# JacdacRgbBar8Ec30_122.net
KiCad netlist of a schematic drawn in Altium Designer
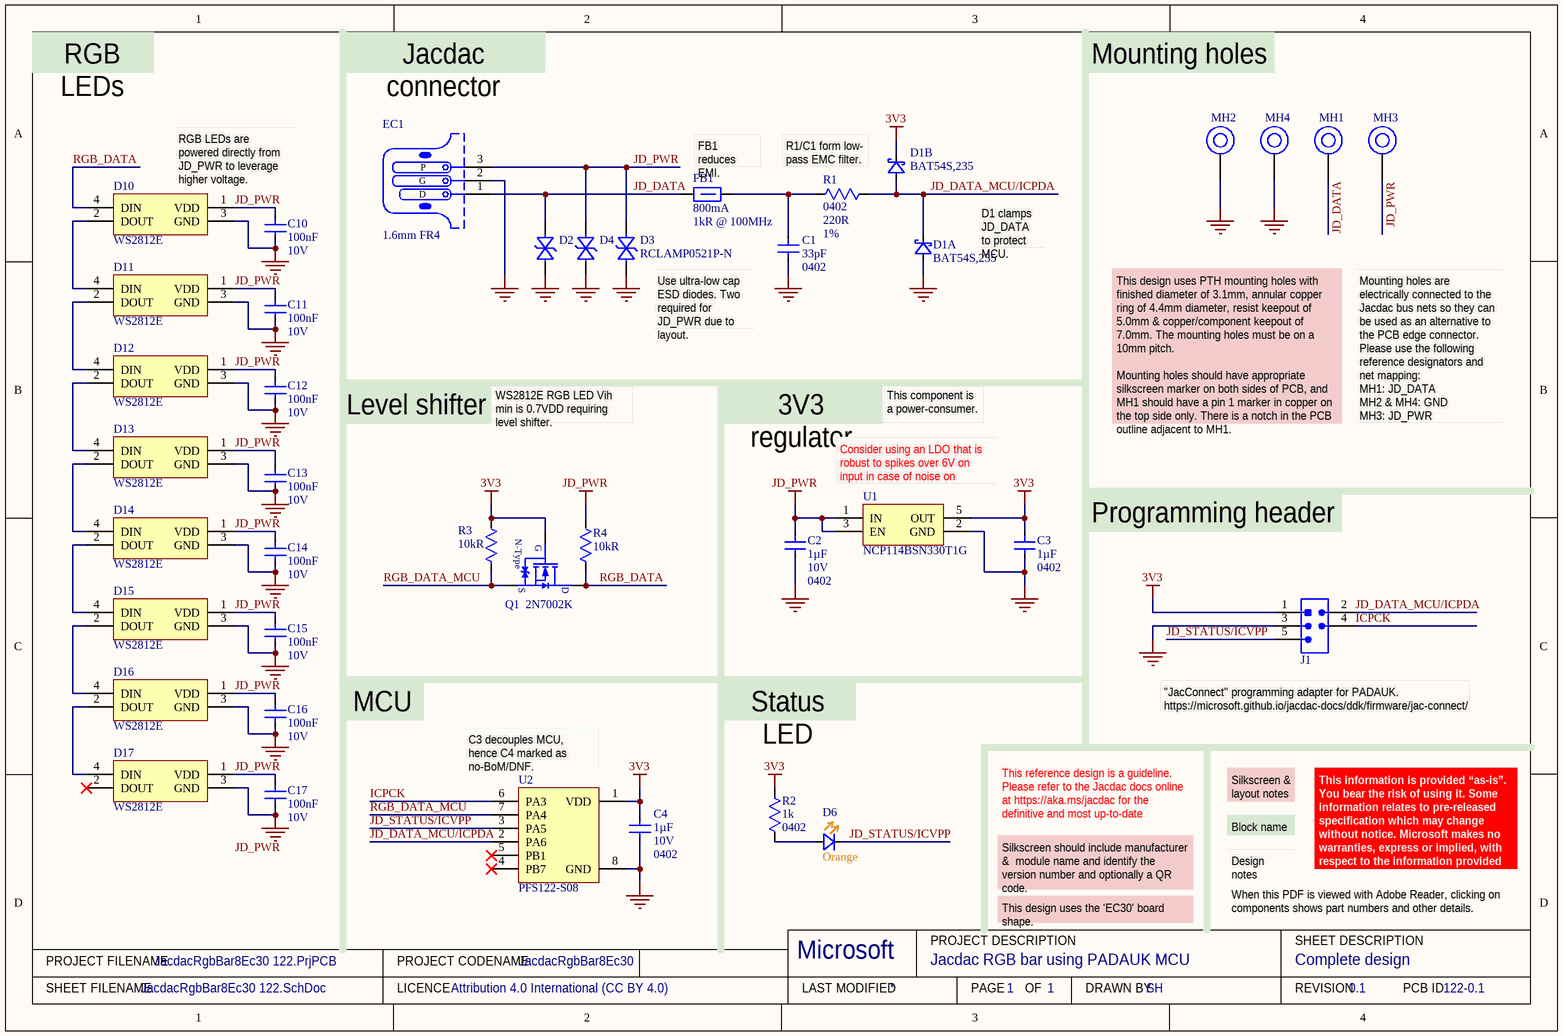
[diagram p0: JacdacRgbBar8Ec30 122.SchDoc]

(export (version "E")
  (design (tool "Eeschema 10.0.6"))
  (components
    (comp (ref "C1")
      (value "CL05C330JB5NNNC")
      (footprint "C0402_0.55MM - without outline")
      (description "CAP CER 33PF 50V C0G/NP0 0402")
      (fields
        (field (name "MANUFACTURER") "Samsung")
        (field (name "CASE CODE (IMPERIAL)") "0402")
        (field (name "TOLERANCE") "5%")
        (field (name "CAPACITANCE") "33pF")
      )
      (libsource (lib "Samsung") (part "CL05C330JB5NNNC"))
    )
    (comp (ref "C2")
      (value "CL05A105KP5NNNC")
      (footprint "C0402_0.55MM - without outline")
      (description "CAP CER 1UF 10V X5R 0402")
      (fields
        (field (name "MANUFACTURER") "Samsung")
        (field (name "TOLERANCE") "10%")
        (field (name "CAPACITANCE") "1µF")
        (field (name "VOLTAGE RATING") "10V")
        (field (name "CASE CODE (IMPERIAL)") "0402")
        (field (name "CREATED") "DG")
        (field (name "CHECKED") "?")
      )
      (libsource (lib "Samsung") (part "CL05A105KP5NNNC"))
    )
    (comp (ref "C3")
      (value "CL05A105KP5NNNC")
      (footprint "C0402_0.55MM - without outline")
      (description "CAP CER 1UF 10V X5R 0402")
      (fields
        (field (name "MANUFACTURER") "Samsung")
        (field (name "TOLERANCE") "10%")
        (field (name "CAPACITANCE") "1µF")
        (field (name "CASE CODE (IMPERIAL)") "0402")
        (field (name "CREATED") "DG")
        (field (name "CHECKED") "?")
      )
      (libsource (lib "Samsung") (part "CL05A105KP5NNNC"))
    )
    (comp (ref "C4")
      (value "CL05A105KP5NNNC")
      (footprint "C0402_0.55MM - without outline")
      (description "CAP CER 1UF 10V X5R 0402")
      (fields
        (field (name "MANUFACTURER") "Samsung")
        (field (name "TOLERANCE") "10%")
        (field (name "CAPACITANCE") "1µF")
        (field (name "VOLTAGE RATING") "10V")
        (field (name "CASE CODE (IMPERIAL)") "0402")
        (field (name "CREATED") "DG")
        (field (name "CHECKED") "?")
      )
      (libsource (lib "Samsung") (part "CL05A105KP5NNNC"))
    )
    (comp (ref "C10")
      (value "CL05B104KP5NNNC")
      (footprint "C0402_0.55MM - without outline")
      (description "CAP CER 0.1UF 10V X7R 0402")
      (fields
        (field (name "MANUFACTURER") "Samsung")
        (field (name "CAPACITANCE") "100nF")
        (field (name "TOLERANCE") "10%")
        (field (name "VOLTAGE RATING") "10V")
        (field (name "CREATED") "DG")
        (field (name "CHECKED") "?")
      )
      (libsource (lib "Samsung") (part "CL05B104KP5NNNC"))
    )
    (comp (ref "C11")
      (value "CL05B104KP5NNNC")
      (footprint "C0402_0.55MM - without outline")
      (description "CAP CER 0.1UF 10V X7R 0402")
      (fields
        (field (name "MANUFACTURER") "Samsung")
        (field (name "CAPACITANCE") "100nF")
        (field (name "TOLERANCE") "10%")
        (field (name "VOLTAGE RATING") "10V")
        (field (name "CREATED") "DG")
        (field (name "CHECKED") "?")
      )
      (libsource (lib "Samsung") (part "CL05B104KP5NNNC"))
    )
    (comp (ref "C12")
      (value "CL05B104KP5NNNC")
      (footprint "C0402_0.55MM - without outline")
      (description "CAP CER 0.1UF 10V X7R 0402")
      (fields
        (field (name "MANUFACTURER") "Samsung")
        (field (name "CAPACITANCE") "100nF")
        (field (name "TOLERANCE") "10%")
        (field (name "VOLTAGE RATING") "10V")
        (field (name "CREATED") "DG")
        (field (name "CHECKED") "?")
      )
      (libsource (lib "Samsung") (part "CL05B104KP5NNNC"))
    )
    (comp (ref "C13")
      (value "CL05B104KP5NNNC")
      (footprint "C0402_0.55MM - without outline")
      (description "CAP CER 0.1UF 10V X7R 0402")
      (fields
        (field (name "MANUFACTURER") "Samsung")
        (field (name "CAPACITANCE") "100nF")
        (field (name "TOLERANCE") "10%")
        (field (name "VOLTAGE RATING") "10V")
        (field (name "CREATED") "DG")
        (field (name "CHECKED") "?")
      )
      (libsource (lib "Samsung") (part "CL05B104KP5NNNC"))
    )
    (comp (ref "C14")
      (value "CL05B104KP5NNNC")
      (footprint "C0402_0.55MM - without outline")
      (description "CAP CER 0.1UF 10V X7R 0402")
      (fields
        (field (name "MANUFACTURER") "Samsung")
        (field (name "CAPACITANCE") "100nF")
        (field (name "TOLERANCE") "10%")
        (field (name "VOLTAGE RATING") "10V")
        (field (name "CREATED") "DG")
        (field (name "CHECKED") "?")
      )
      (libsource (lib "Samsung") (part "CL05B104KP5NNNC"))
    )
    (comp (ref "C15")
      (value "CL05B104KP5NNNC")
      (footprint "C0402_0.55MM - without outline")
      (description "CAP CER 0.1UF 10V X7R 0402")
      (fields
        (field (name "MANUFACTURER") "Samsung")
        (field (name "CAPACITANCE") "100nF")
        (field (name "TOLERANCE") "10%")
        (field (name "VOLTAGE RATING") "10V")
        (field (name "CREATED") "DG")
        (field (name "CHECKED") "?")
      )
      (libsource (lib "Samsung") (part "CL05B104KP5NNNC"))
    )
    (comp (ref "C16")
      (value "CL05B104KP5NNNC")
      (footprint "C0402_0.55MM - without outline")
      (description "CAP CER 0.1UF 10V X7R 0402")
      (fields
        (field (name "MANUFACTURER") "Samsung")
        (field (name "CAPACITANCE") "100nF")
        (field (name "TOLERANCE") "10%")
        (field (name "VOLTAGE RATING") "10V")
        (field (name "CREATED") "DG")
        (field (name "CHECKED") "?")
      )
      (libsource (lib "Samsung") (part "CL05B104KP5NNNC"))
    )
    (comp (ref "C17")
      (value "CL05B104KP5NNNC")
      (footprint "C0402_0.55MM - without outline")
      (description "CAP CER 0.1UF 10V X7R 0402")
      (fields
        (field (name "MANUFACTURER") "Samsung")
        (field (name "CAPACITANCE") "100nF")
        (field (name "TOLERANCE") "10%")
        (field (name "VOLTAGE RATING") "10V")
        (field (name "CREATED") "DG")
        (field (name "CHECKED") "?")
      )
      (libsource (lib "Samsung") (part "CL05B104KP5NNNC"))
    )
    (comp (ref "D1")
      (value "BAT54S")
      (footprint "NXP-BAT54S-TO-236AB - without outline")
      (description "DIODE ARRAY SCHOTTKY 30V SOT23")
      (fields (field (name "MANUFACTURER") "Nexperia") (field (name "MANUFACTURER PART NUMBER") "BAT54S,235"))
      (libsource (lib "NXP") (part "BAT54S"))
    )
    (comp (ref "D2")
      (value "RCLAMP0521P-N")
      (footprint "0402:TVS 0402 - XL")
      (description "Bidirectional 5V (Max) 6V 16V 3.5A (8/20us) 0402 TVS RoHS")
      (fields
        (field (name "MANUFACTURER") "Born Semiconductor")
        (field (name "CREATED BY") "D Gakure")
        (field (name "CHECKED BY") "?")
      )
      (libsource (lib "BornSemiconductor") (part "RCLAMP0521P-N"))
    )
    (comp (ref "D3")
      (value "RCLAMP0521P-N")
      (footprint "0402:TVS 0402 - XL")
      (description "Bidirectional 5V (Max) 6V 16V 3.5A (8/20us) 0402 TVS RoHS")
      (fields
        (field (name "MANUFACTURER") "Born Semiconductor")
        (field (name "MANUFACTURER PART NUMBER") "RCLAMP0521P-N")
        (field (name "CREATED BY") "D Gakure")
        (field (name "CHECKED BY") "?")
      )
      (libsource (lib "BornSemiconductor") (part "RCLAMP0521P-N"))
    )
    (comp (ref "D4")
      (value "RCLAMP0521P-N")
      (footprint "0402:TVS 0402 - XL")
      (description "Bidirectional 5V (Max) 6V 16V 3.5A (8/20us) 0402 TVS RoHS")
      (fields
        (field (name "MANUFACTURER") "Born Semiconductor")
        (field (name "CREATED BY") "D Gakure")
        (field (name "CHECKED BY") "?")
      )
      (libsource (lib "BornSemiconductor") (part "RCLAMP0521P-N"))
    )
    (comp (ref "D6")
      (value "~")
      (footprint "0603 Orange - without outline")
      (description "LED ORANGE DIFFUSED 1608 SMD")
      (fields
        (field (name "MANUFACTURER") "Everlight Elec")
        (field (name "MANUFACTURER PART NUMBER") "19-217/S2C-AQ1R1B/3T")
        (field (name "COLOUR") "Orange")
      )
      (libsource (lib "EverlightElec") (part "19-217/S2C-AQ1R1B/3T"))
    )
    (comp (ref "D10")
      (value "WS2812E")
      (footprint "WS2812E-5050")
      (description "WS2812E 5050 RGB LED WITH INTEGRATED DRIVER")
      (fields (field (name "MANUFACTURER") "Worldsemi") (field (name "MANUFACTURER PART NUMBER") "WS2812E"))
      (libsource (lib "WorldSemi") (part "WS2812E-5050"))
    )
    (comp (ref "D11")
      (value "WS2812E")
      (footprint "WS2812E-5050")
      (description "WS2812E 5050 RGB LED WITH INTEGRATED DRIVER")
      (fields (field (name "MANUFACTURER") "Worldsemi") (field (name "MANUFACTURER PART NUMBER") "WS2812E"))
      (libsource (lib "WorldSemi") (part "WS2812E-5050"))
    )
    (comp (ref "D12")
      (value "WS2812E")
      (footprint "WS2812E-5050")
      (description "WS2812E 5050 RGB LED WITH INTEGRATED DRIVER")
      (fields (field (name "MANUFACTURER") "Worldsemi") (field (name "MANUFACTURER PART NUMBER") "WS2812E"))
      (libsource (lib "WorldSemi") (part "WS2812E-5050"))
    )
    (comp (ref "D13")
      (value "WS2812E")
      (footprint "WS2812E-5050")
      (description "WS2812E 5050 RGB LED WITH INTEGRATED DRIVER")
      (fields (field (name "MANUFACTURER") "Worldsemi") (field (name "MANUFACTURER PART NUMBER") "WS2812E"))
      (libsource (lib "WorldSemi") (part "WS2812E-5050"))
    )
    (comp (ref "D14")
      (value "WS2812E")
      (footprint "WS2812E-5050")
      (description "WS2812E 5050 RGB LED WITH INTEGRATED DRIVER")
      (fields (field (name "MANUFACTURER") "Worldsemi") (field (name "MANUFACTURER PART NUMBER") "WS2812E"))
      (libsource (lib "WorldSemi") (part "WS2812E-5050"))
    )
    (comp (ref "D15")
      (value "WS2812E")
      (footprint "WS2812E-5050")
      (description "WS2812E 5050 RGB LED WITH INTEGRATED DRIVER")
      (fields (field (name "MANUFACTURER") "Worldsemi") (field (name "MANUFACTURER PART NUMBER") "WS2812E"))
      (libsource (lib "WorldSemi") (part "WS2812E-5050"))
    )
    (comp (ref "D16")
      (value "WS2812E")
      (footprint "WS2812E-5050")
      (description "WS2812E 5050 RGB LED WITH INTEGRATED DRIVER")
      (fields (field (name "MANUFACTURER") "Worldsemi") (field (name "MANUFACTURER PART NUMBER") "WS2812E"))
      (libsource (lib "WorldSemi") (part "WS2812E-5050"))
    )
    (comp (ref "D17")
      (value "WS2812E")
      (footprint "WS2812E-5050")
      (description "WS2812E 5050 RGB LED WITH INTEGRATED DRIVER")
      (fields (field (name "MANUFACTURER") "Worldsemi") (field (name "MANUFACTURER PART NUMBER") "WS2812E"))
      (libsource (lib "WorldSemi") (part "WS2812E-5050"))
    )
    (comp (ref "EC1")
      (value "3 pin JACDAC edge connector")
      (footprint "JACDAC_edge_connector:JACDAC_EDGE_CONNECTOR_NO_TRACES")
      (description "3 pin Jacdac edge connector 1.27mm pitch")
      (fields
        (field (name "MANUFACTURER PART NUMBER") "JACDAC_EDGE_CONNECTOR")
        (field (name "PCB TYPE") "1.6mm FR4")
        (field (name "CHECKED BY") "?")
        (field (name "CREATED BY") "D. Gakure")
      )
      (libsource (lib "generic-con") (part "Jacdac edge connector"))
    )
    (comp (ref "FB1")
      (value "TDK MPZ1608S102ATA00")
      (footprint "TDK MPZ1608 0.8mm - without outline")
      (description "0603 1k@100MHz 0.8A chip")
      (fields
        (field (name "TOLERANCE") "25%")
        (field (name "MANUFACTURER") "TDK")
        (field (name "CURRENT RATING") "800mA")
        (field (name "IMPEDANCE") "1kR @ 100MHz")
      )
      (libsource (lib "TDK") (part "TDK MPZ1608S102ATA00"))
    )
    (comp (ref "J1")
      (value "Hack Connect Mini 1.27 mm pitch 2-row")
      (footprint "HackConnect:HACK_CONNECT_MINI_5_X_1_27_0.559mm_TH")
      (libsource (lib "generic-con") (part "HACK_CONNECT_MINI"))
    )
    (comp (ref "MH1")
      (value "MH_7.0MMK_4.4MMC_3.1MMD_PTH")
      (footprint "MH_7.0MMK_4.4MMC_3.1MMD_PTH:MH_7.0MMK_4.4MMC_3.1MMD_PTH")
      (description "Mounting Hole 7.0mm keepout, 4.4mm annualar ring and 3.1mm Drill PTH")
      (libsource (lib "generic") (part "MH_7.0MMK_4.4MMC_3.1MMD_PTH"))
    )
    (comp (ref "MH2")
      (value "MH_7.0MMK_4.4MMC_3.1MMD_PTH")
      (footprint "MH_7.0MMK_4.4MMC_3.1MMD_PTH:MH_7.0MMK_4.4MMC_3.1MMD_PTH")
      (description "Mounting Hole 7.0mm keepout, 4.4mm annualar ring and 3.1mm Drill PTH")
      (libsource (lib "generic") (part "MH_7.0MMK_4.4MMC_3.1MMD_PTH"))
    )
    (comp (ref "MH3")
      (value "MH_7.0MMK_4.4MMC_3.1MMD_PTH")
      (footprint "MH_7.0MMK_4.4MMC_3.1MMD_PTH:MH_7.0MMK_4.4MMC_3.1MMD_PTH")
      (description "Mounting Hole 7.0mm keepout, 4.4mm annualar ring and 3.1mm Drill PTH")
      (libsource (lib "generic") (part "MH_7.0MMK_4.4MMC_3.1MMD_PTH"))
    )
    (comp (ref "MH4")
      (value "MH_7.0MMK_4.4MMC_3.1MMD_PTH")
      (footprint "MH_7.0MMK_4.4MMC_3.1MMD_PTH:MH_7.0MMK_4.4MMC_3.1MMD_PTH")
      (description "Mounting Hole 7.0mm keepout, 4.4mm annualar ring and 3.1mm Drill PTH")
      (libsource (lib "generic") (part "MH_7.0MMK_4.4MMC_3.1MMD_PTH"))
    )
    (comp (ref "Q1")
      (value "2N7002K")
      (footprint "SOT-23")
      (description "MOSFET Transistor, N Channel, 300 mA, 60 V, 2 ohm, 10 V, 2.5 V")
      (fields
        (field (name "MANUFACTURER") "ON Semiconductor / Fairchild")
        (field (name "VOLTAGE") "60V")
        (field (name "MANUFACTURER PART NUMBER") "2N7002K")
        (field (name "CREATED BY") "D. Gakure")
        (field (name "CHECKED BY") "?")
      )
      (libsource (lib "OnSemiconductor") (part "2N7002K (2)"))
    )
    (comp (ref "R1")
      (value "RC0402FR-07220RL")
      (footprint "R0402 - Without outline")
      (description "RES SMD 220 OHM 1% 1/16W 0402")
      (fields
        (field (name "MANUFACTURER") "Yageo")
        (field (name "CASE CODE (IMPERIAL)") "0402")
        (field (name "RESISTANCE") "220R")
        (field (name "TOLERANCE") "1%")
        (field (name "CREATED") "D.G")
        (field (name "CHECKED") "?")
      )
      (libsource (lib "Yageo") (part "RC0402FR-07220RL"))
    )
    (comp (ref "R2")
      (value "RC0402FR-071KL")
      (footprint "R0402 - Without outline")
      (description "RES SMD 1K OHM 1% 1/16W 0402")
      (fields
        (field (name "MANUFACTURER") "Yageo")
        (field (name "CASE CODE (IMPERIAL)") "0402")
        (field (name "TOLERANCE") "1%")
        (field (name "RESISTANCE") "1k")
        (field (name "CREATED") "D.G")
        (field (name "CHECKED") "?")
      )
      (libsource (lib "Yageo") (part "RC0402FR-071KL"))
    )
    (comp (ref "R3")
      (value "10k")
      (footprint "R0402 - Without outline")
      (description "RES SMD 10K OHM 1% 1/16W 0402")
      (fields
        (field (name "MANUFACTURER") "Yageo")
        (field (name "MANUFACTURER PART NUMBER") "RC0402FR-0710KL")
        (field (name "RESISTANCE") "10kR")
        (field (name "CHECKED") "?")
        (field (name "CREATED") "DG")
      )
      (libsource (lib "Yageo") (part "RC0402FR-0710KL"))
    )
    (comp (ref "R4")
      (value "10k")
      (footprint "R0402 - Without outline")
      (description "RES SMD 10K OHM 1% 1/16W 0402")
      (fields
        (field (name "MANUFACTURER") "Yageo")
        (field (name "MANUFACTURER PART NUMBER") "RC0402FR-0710KL")
        (field (name "RESISTANCE") "10kR")
        (field (name "CHECKED") "?")
        (field (name "CREATED") "DG")
      )
      (libsource (lib "Yageo") (part "RC0402FR-0710KL"))
    )
    (comp (ref "U1")
      (value "LDO 3.3V/300 mA")
      (footprint "ON_SEMI-SOT23-5 - without outline")
      (description "CMOS Low Dropout Regulator (LDO), 300 mA 3.3V, Non-Active Discharge, TSOP5")
      (fields
        (field (name "MANUFACTURER") "ON Semiconductor")
        (field (name "MANUFACTURER PART NUMBER") "NCP114BSN330T1G")
      )
      (libsource (lib "OnSemiconductor") (part "NCP114BSN330T1G"))
    )
    (comp (ref "U2")
      (value "PFS122-S08")
      (footprint "PADAUK-SOP-8:SOP-8")
      (description "8bit MTP MCU with 12-bit ADC")
      (fields (field (name "MANUFACTURER") "PADAUK") (field (name "MANUFACTURER PART NUMBER") "PFS122-S08"))
      (libsource (lib "PADAUK") (part "PFS122-SO8"))
    )
  )
  (nets
    (net (code "1") (name "/ICPCK") (class "Default")
      (node (ref "J1") (pin "4") (pinfunction "SWCLK_4") (pintype "passive"))
      (node (ref "U2") (pin "6") (pinfunction "PA3_6") (pintype "passive"))
    )
    (net (code "2") (name "/JD_DATA") (class "Default")
      (node (ref "D2") (pin "1") (pinfunction "K_1") (pintype "passive"))
      (node (ref "EC1") (pin "1") (pinfunction "D_1") (pintype "passive"))
      (node (ref "FB1") (pin "1") (pinfunction "1_1") (pintype "passive"))
      (node (ref "MH1") (pin "1") (pinfunction "1_1") (pintype "passive"))
    )
    (net (code "3") (name "/JD_DATA_MCU{slash}ICPDA") (class "Default")
      (node (ref "D1") (pin "3") (pinfunction "A_3") (pintype "passive"))
      (node (ref "J1") (pin "2") (pinfunction "SWDIO_2") (pintype "passive"))
      (node (ref "R1") (pin "1") (pinfunction "1_1") (pintype "passive"))
      (node (ref "U2") (pin "2") (pinfunction "PA6_2") (pintype "passive"))
    )
    (net (code "4") (name "/JD_STATUS{slash}ICVPP") (class "Default")
      (node (ref "D6") (pin "1") (pinfunction "K_1") (pintype "passive"))
      (node (ref "J1") (pin "5") (pinfunction "RESET_5") (pintype "passive"))
      (node (ref "U2") (pin "3") (pinfunction "PA5_3") (pintype "passive"))
    )
    (net (code "5") (name "/RGB_DATA") (class "Default")
      (node (ref "D10") (pin "4") (pinfunction "DIN_4") (pintype "passive"))
      (node (ref "Q1") (pin "3") (pinfunction "D_3") (pintype "passive"))
      (node (ref "R4") (pin "2") (pinfunction "2_2") (pintype "passive"))
    )
    (net (code "6") (name "/RGB_DATA_MCU") (class "Default")
      (node (ref "Q1") (pin "2") (pinfunction "S_2") (pintype "passive"))
      (node (ref "R3") (pin "2") (pinfunction "2_2") (pintype "passive"))
      (node (ref "U2") (pin "7") (pinfunction "PA4_7") (pintype "passive"))
    )
    (net (code "7") (name "3V3") (class "Default")
      (node (ref "C3") (pin "2") (pinfunction "2_2") (pintype "passive"))
      (node (ref "C4") (pin "2") (pinfunction "2_2") (pintype "passive"))
      (node (ref "D1") (pin "2") (pinfunction "K_2") (pintype "passive"))
      (node (ref "J1") (pin "1") (pinfunction "VCC_1") (pintype "passive"))
      (node (ref "Q1") (pin "1") (pinfunction "G_1") (pintype "passive"))
      (node (ref "R2") (pin "2") (pinfunction "2_2") (pintype "passive"))
      (node (ref "R3") (pin "1") (pinfunction "1_1") (pintype "passive"))
      (node (ref "U1") (pin "5") (pinfunction "OUT_5") (pintype "passive"))
      (node (ref "U2") (pin "1") (pinfunction "VDD_1") (pintype "passive"))
    )
    (net (code "8") (name "GND") (class "Default")
      (node (ref "C1") (pin "1") (pinfunction "1_1") (pintype "passive"))
      (node (ref "C10") (pin "1") (pinfunction "1_1") (pintype "passive"))
      (node (ref "C11") (pin "1") (pinfunction "1_1") (pintype "passive"))
      (node (ref "C12") (pin "1") (pinfunction "1_1") (pintype "passive"))
      (node (ref "C13") (pin "1") (pinfunction "1_1") (pintype "passive"))
      (node (ref "C14") (pin "1") (pinfunction "1_1") (pintype "passive"))
      (node (ref "C15") (pin "1") (pinfunction "1_1") (pintype "passive"))
      (node (ref "C16") (pin "1") (pinfunction "1_1") (pintype "passive"))
      (node (ref "C17") (pin "1") (pinfunction "1_1") (pintype "passive"))
      (node (ref "C2") (pin "1") (pinfunction "1_1") (pintype "passive"))
      (node (ref "C3") (pin "1") (pinfunction "1_1") (pintype "passive"))
      (node (ref "C4") (pin "1") (pinfunction "1_1") (pintype "passive"))
      (node (ref "D1") (pin "1") (pinfunction "A_1") (pintype "passive"))
      (node (ref "D10") (pin "3") (pinfunction "GND_3") (pintype "passive"))
      (node (ref "D11") (pin "3") (pinfunction "GND_3") (pintype "passive"))
      (node (ref "D12") (pin "3") (pinfunction "GND_3") (pintype "passive"))
      (node (ref "D13") (pin "3") (pinfunction "GND_3") (pintype "passive"))
      (node (ref "D14") (pin "3") (pinfunction "GND_3") (pintype "passive"))
      (node (ref "D15") (pin "3") (pinfunction "GND_3") (pintype "passive"))
      (node (ref "D16") (pin "3") (pinfunction "GND_3") (pintype "passive"))
      (node (ref "D17") (pin "3") (pinfunction "GND_3") (pintype "passive"))
      (node (ref "D2") (pin "2") (pinfunction "A_2") (pintype "passive"))
      (node (ref "D3") (pin "2") (pinfunction "A_2") (pintype "passive"))
      (node (ref "D4") (pin "2") (pinfunction "A_2") (pintype "passive"))
      (node (ref "EC1") (pin "2") (pinfunction "G_2") (pintype "passive"))
      (node (ref "J1") (pin "3") (pinfunction "GND_3") (pintype "passive"))
      (node (ref "MH2") (pin "1") (pinfunction "1_1") (pintype "passive"))
      (node (ref "MH4") (pin "1") (pinfunction "1_1") (pintype "passive"))
      (node (ref "U1") (pin "2") (pinfunction "GND_2") (pintype "passive"))
      (node (ref "U2") (pin "8") (pinfunction "GND_8") (pintype "passive"))
    )
    (net (code "9") (name "JD_PWR") (class "Default")
      (node (ref "C10") (pin "2") (pinfunction "2_2") (pintype "passive"))
      (node (ref "C11") (pin "2") (pinfunction "2_2") (pintype "passive"))
      (node (ref "C12") (pin "2") (pinfunction "2_2") (pintype "passive"))
      (node (ref "C13") (pin "2") (pinfunction "2_2") (pintype "passive"))
      (node (ref "C14") (pin "2") (pinfunction "2_2") (pintype "passive"))
      (node (ref "C15") (pin "2") (pinfunction "2_2") (pintype "passive"))
      (node (ref "C16") (pin "2") (pinfunction "2_2") (pintype "passive"))
      (node (ref "C17") (pin "2") (pinfunction "2_2") (pintype "passive"))
      (node (ref "C2") (pin "2") (pinfunction "2_2") (pintype "passive"))
      (node (ref "D10") (pin "1") (pinfunction "VDD_1") (pintype "passive"))
      (node (ref "D11") (pin "1") (pinfunction "VDD_1") (pintype "passive"))
      (node (ref "D12") (pin "1") (pinfunction "VDD_1") (pintype "passive"))
      (node (ref "D13") (pin "1") (pinfunction "VDD_1") (pintype "passive"))
      (node (ref "D14") (pin "1") (pinfunction "VDD_1") (pintype "passive"))
      (node (ref "D15") (pin "1") (pinfunction "VDD_1") (pintype "passive"))
      (node (ref "D16") (pin "1") (pinfunction "VDD_1") (pintype "passive"))
      (node (ref "D17") (pin "1") (pinfunction "VDD_1") (pintype "passive"))
      (node (ref "D3") (pin "1") (pinfunction "K_1") (pintype "passive"))
      (node (ref "D4") (pin "1") (pinfunction "K_1") (pintype "passive"))
      (node (ref "EC1") (pin "3") (pinfunction "P_3") (pintype "passive"))
      (node (ref "MH3") (pin "1") (pinfunction "1_1") (pintype "passive"))
      (node (ref "R4") (pin "1") (pinfunction "1_1") (pintype "passive"))
      (node (ref "U1") (pin "1") (pinfunction "IN_1") (pintype "passive"))
      (node (ref "U1") (pin "3") (pinfunction "EN_3") (pintype "passive"))
    )
    (net (code "10") (name "Net-(C1-Pad2)") (class "Default")
      (node (ref "C1") (pin "2") (pinfunction "2_2") (pintype "passive"))
      (node (ref "FB1") (pin "2") (pinfunction "2_2") (pintype "passive"))
      (node (ref "R1") (pin "2") (pinfunction "2_2") (pintype "passive"))
    )
    (net (code "11") (name "Net-(D6-A)") (class "Default")
      (node (ref "D6") (pin "2") (pinfunction "A_2") (pintype "passive"))
      (node (ref "R2") (pin "1") (pinfunction "1_1") (pintype "passive"))
    )
    (net (code "12") (name "Net-(D10-DOUT)") (class "Default")
      (node (ref "D10") (pin "2") (pinfunction "DOUT_2") (pintype "passive"))
      (node (ref "D11") (pin "4") (pinfunction "DIN_4") (pintype "passive"))
    )
    (net (code "13") (name "Net-(D11-DOUT)") (class "Default")
      (node (ref "D11") (pin "2") (pinfunction "DOUT_2") (pintype "passive"))
      (node (ref "D12") (pin "4") (pinfunction "DIN_4") (pintype "passive"))
    )
    (net (code "14") (name "Net-(D12-DOUT)") (class "Default")
      (node (ref "D12") (pin "2") (pinfunction "DOUT_2") (pintype "passive"))
      (node (ref "D13") (pin "4") (pinfunction "DIN_4") (pintype "passive"))
    )
    (net (code "15") (name "Net-(D13-DOUT)") (class "Default")
      (node (ref "D13") (pin "2") (pinfunction "DOUT_2") (pintype "passive"))
      (node (ref "D14") (pin "4") (pinfunction "DIN_4") (pintype "passive"))
    )
    (net (code "16") (name "Net-(D14-DOUT)") (class "Default")
      (node (ref "D14") (pin "2") (pinfunction "DOUT_2") (pintype "passive"))
      (node (ref "D15") (pin "4") (pinfunction "DIN_4") (pintype "passive"))
    )
    (net (code "17") (name "Net-(D15-DOUT)") (class "Default")
      (node (ref "D15") (pin "2") (pinfunction "DOUT_2") (pintype "passive"))
      (node (ref "D16") (pin "4") (pinfunction "DIN_4") (pintype "passive"))
    )
    (net (code "18") (name "Net-(D16-DOUT)") (class "Default")
      (node (ref "D16") (pin "2") (pinfunction "DOUT_2") (pintype "passive"))
      (node (ref "D17") (pin "4") (pinfunction "DIN_4") (pintype "passive"))
    )
    (net (code "19") (name "unconnected-(D17-DOUT-Pad2)") (class "Default")
      (node (ref "D17") (pin "2") (pinfunction "DOUT_2") (pintype "passive+no_connect"))
    )
    (net (code "20") (name "unconnected-(U2-PB1-Pad5)") (class "Default")
      (node (ref "U2") (pin "5") (pinfunction "PB1_5") (pintype "passive+no_connect"))
    )
    (net (code "21") (name "unconnected-(U2-PB7-Pad4)") (class "Default")
      (node (ref "U2") (pin "4") (pinfunction "PB7_4") (pintype "passive+no_connect"))
    )
  )
)
